# Nixie_noTube_final.net
KiCad netlist of a schematic drawn in EAGLE
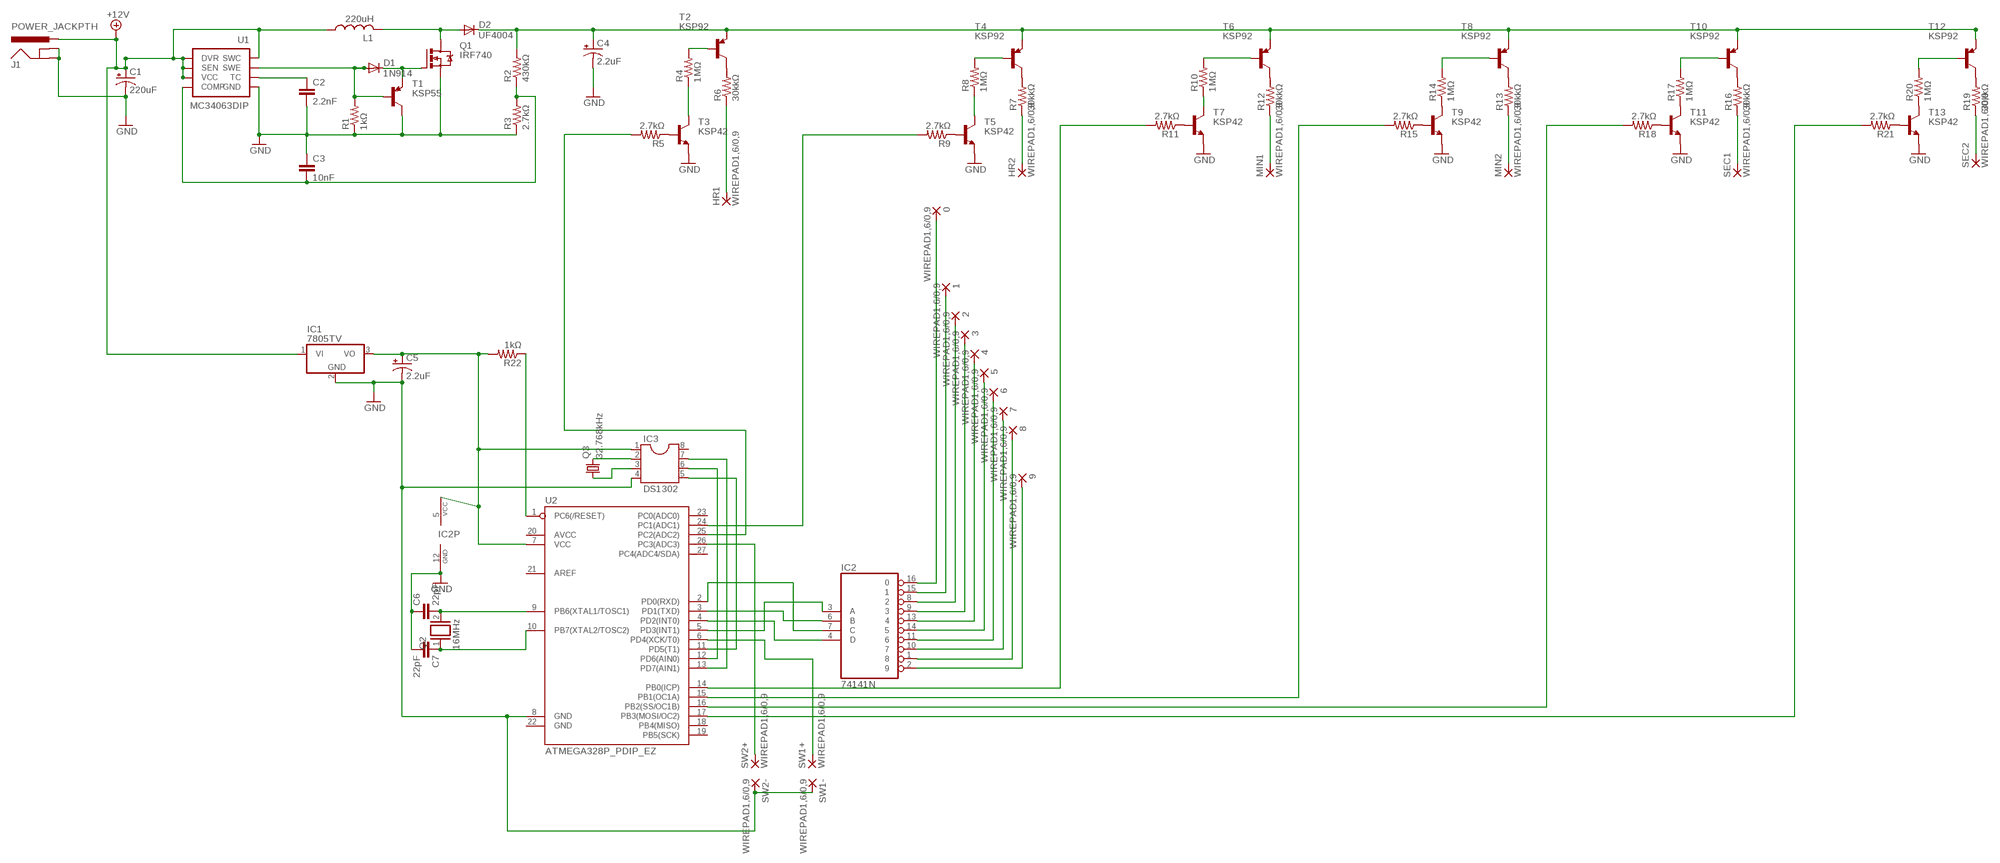
[diagram p0: schematic, sheet 1]

(export (version "E")
  (design (tool "Eeschema 10.0.6"))
  (components
    (comp (ref "0")
      (value "WIREPAD1,6/0,9")
      (footprint "eagle-import:1,6_0,9")
      (libsource (lib "eagle-import") (part "WIREPAD1,6/0,9"))
    )
    (comp (ref "1")
      (value "WIREPAD1,6/0,9")
      (footprint "eagle-import:1,6_0,9")
      (libsource (lib "eagle-import") (part "WIREPAD1,6/0,9"))
    )
    (comp (ref "2")
      (value "WIREPAD1,6/0,9")
      (footprint "eagle-import:1,6_0,9")
      (libsource (lib "eagle-import") (part "WIREPAD1,6/0,9"))
    )
    (comp (ref "3")
      (value "WIREPAD1,6/0,9")
      (footprint "eagle-import:1,6_0,9")
      (libsource (lib "eagle-import") (part "WIREPAD1,6/0,9"))
    )
    (comp (ref "4")
      (value "WIREPAD1,6/0,9")
      (footprint "eagle-import:1,6_0,9")
      (libsource (lib "eagle-import") (part "WIREPAD1,6/0,9"))
    )
    (comp (ref "5")
      (value "WIREPAD1,6/0,9")
      (footprint "eagle-import:1,6_0,9")
      (libsource (lib "eagle-import") (part "WIREPAD1,6/0,9"))
    )
    (comp (ref "6")
      (value "WIREPAD1,6/0,9")
      (footprint "eagle-import:1,6_0,9")
      (libsource (lib "eagle-import") (part "WIREPAD1,6/0,9"))
    )
    (comp (ref "7")
      (value "WIREPAD1,6/0,9")
      (footprint "eagle-import:1,6_0,9")
      (libsource (lib "eagle-import") (part "WIREPAD1,6/0,9"))
    )
    (comp (ref "8")
      (value "WIREPAD1,6/0,9")
      (footprint "eagle-import:1,6_0,9")
      (libsource (lib "eagle-import") (part "WIREPAD1,6/0,9"))
    )
    (comp (ref "9")
      (value "WIREPAD1,6/0,9")
      (footprint "eagle-import:1,6_0,9")
      (libsource (lib "eagle-import") (part "WIREPAD1,6/0,9"))
    )
    (comp (ref "C1")
      (value "220uF")
      (footprint "eagle-import:CPOL-RADIAL-100UF-25V")
      (libsource (lib "eagle-import") (part "CAP_POLPTH1"))
    )
    (comp (ref "C2")
      (value "2.2nF")
      (footprint "eagle-import:CAP-PTH-SMALLEZ")
      (libsource (lib "eagle-import") (part "CAPEZ"))
    )
    (comp (ref "C3")
      (value "10nF")
      (footprint "eagle-import:CAP-PTH-SMALLEZ")
      (libsource (lib "eagle-import") (part "CAPEZ"))
    )
    (comp (ref "C4")
      (value "2.2uF")
      (footprint "eagle-import:CPOL-RADIAL-100UF-25V")
      (libsource (lib "eagle-import") (part "CAP_POLPTH1"))
    )
    (comp (ref "C5")
      (value "2.2uF")
      (footprint "eagle-import:CPOL-RADIAL-100UF-25V")
      (libsource (lib "eagle-import") (part "CAP_POLPTH1"))
    )
    (comp (ref "C6")
      (value "22pF")
      (footprint "eagle-import:C2.5-3")
      (libsource (lib "eagle-import") (part "C2,5-3"))
    )
    (comp (ref "C7")
      (value "22pF")
      (footprint "eagle-import:C2.5-3")
      (libsource (lib "eagle-import") (part "C2,5-3"))
    )
    (comp (ref "D1")
      (value "1N914")
      (footprint "eagle-import:DO41-10")
      (libsource (lib "eagle-import") (part "1N4004"))
    )
    (comp (ref "D2")
      (value "UF4004")
      (footprint "eagle-import:DO41-10")
      (libsource (lib "eagle-import") (part "1N4004"))
    )
    (comp (ref "HR1")
      (value "WIREPAD1,6/0,9")
      (footprint "eagle-import:1,6_0,9")
      (libsource (lib "eagle-import") (part "WIREPAD1,6/0,9"))
    )
    (comp (ref "HR2")
      (value "WIREPAD1,6/0,9")
      (footprint "eagle-import:1,6_0,9")
      (libsource (lib "eagle-import") (part "WIREPAD1,6/0,9"))
    )
    (comp (ref "IC1")
      (value "7805TV")
      (footprint "eagle-import:TO220V")
      (libsource (lib "eagle-import") (part "78TV05"))
    )
    (comp (ref "IC2")
      (value "74141N")
      (footprint "eagle-import:DIL16")
      (libsource (lib "eagle-import") (part "74141N"))
    )
    (comp (ref "IC3")
      (value "DS1302")
      (footprint "eagle-import:DIL08")
      (libsource (lib "eagle-import") (part "DIL8"))
    )
    (comp (ref "J1")
      (value "POWER_JACKPTH")
      (footprint "eagle-import:POWER_JACK_PTH")
      (libsource (lib "eagle-import") (part "POWER_JACKPTH"))
    )
    (comp (ref "L1")
      (value "220uH")
      (footprint "eagle-import:6000-XXXX-RC")
      (libsource (lib "eagle-import") (part "L-US6000-XXX-RC"))
    )
    (comp (ref "MIN1")
      (value "WIREPAD1,6/0,9")
      (footprint "eagle-import:1,6_0,9")
      (libsource (lib "eagle-import") (part "WIREPAD1,6/0,9"))
    )
    (comp (ref "MIN2")
      (value "WIREPAD1,6/0,9")
      (footprint "eagle-import:1,6_0,9")
      (libsource (lib "eagle-import") (part "WIREPAD1,6/0,9"))
    )
    (comp (ref "Q1")
      (value "IRF740")
      (footprint "eagle-import:TO220BV")
      (libsource (lib "eagle-import") (part "IRF740"))
    )
    (comp (ref "Q2")
      (value "16MHz")
      (footprint "eagle-import:QS")
      (libsource (lib "eagle-import") (part "XTAL/S"))
    )
    (comp (ref "Q3")
      (value "32.768kHz")
      (footprint "eagle-import:TC26H")
      (libsource (lib "eagle-import") (part "CRYSTALTC26H"))
    )
    (comp (ref "R1")
      (value "1kΩ")
      (footprint "eagle-import:0204_7")
      (libsource (lib "eagle-import") (part "R-US_0204/7"))
    )
    (comp (ref "R2")
      (value "430kΩ")
      (footprint "eagle-import:0204_7")
      (libsource (lib "eagle-import") (part "R-US_0204/7"))
    )
    (comp (ref "R3")
      (value "2.7kΩ")
      (footprint "eagle-import:0204_7")
      (libsource (lib "eagle-import") (part "R-US_0204/7"))
    )
    (comp (ref "R4")
      (value "1MΩ")
      (footprint "eagle-import:0204_7")
      (libsource (lib "eagle-import") (part "R-US_0204/7"))
    )
    (comp (ref "R5")
      (value "2.7kΩ")
      (footprint "eagle-import:0204_7")
      (libsource (lib "eagle-import") (part "R-US_0204/7"))
    )
    (comp (ref "R6")
      (value "30kkΩ")
      (footprint "eagle-import:0204_7")
      (libsource (lib "eagle-import") (part "R-US_0204/7"))
    )
    (comp (ref "R7")
      (value "30kkΩ")
      (footprint "eagle-import:0204_7")
      (libsource (lib "eagle-import") (part "R-US_0204/7"))
    )
    (comp (ref "R8")
      (value "1MΩ")
      (footprint "eagle-import:0204_7")
      (libsource (lib "eagle-import") (part "R-US_0204/7"))
    )
    (comp (ref "R9")
      (value "2.7kΩ")
      (footprint "eagle-import:0204_7")
      (libsource (lib "eagle-import") (part "R-US_0204/7"))
    )
    (comp (ref "R10")
      (value "1MΩ")
      (footprint "eagle-import:0204_7")
      (libsource (lib "eagle-import") (part "R-US_0204/7"))
    )
    (comp (ref "R11")
      (value "2.7kΩ")
      (footprint "eagle-import:0204_7")
      (libsource (lib "eagle-import") (part "R-US_0204/7"))
    )
    (comp (ref "R12")
      (value "30kkΩ")
      (footprint "eagle-import:0204_7")
      (libsource (lib "eagle-import") (part "R-US_0204/7"))
    )
    (comp (ref "R13")
      (value "30kkΩ")
      (footprint "eagle-import:0204_7")
      (libsource (lib "eagle-import") (part "R-US_0204/7"))
    )
    (comp (ref "R14")
      (value "1MΩ")
      (footprint "eagle-import:0204_7")
      (libsource (lib "eagle-import") (part "R-US_0204/7"))
    )
    (comp (ref "R15")
      (value "2.7kΩ")
      (footprint "eagle-import:0204_7")
      (libsource (lib "eagle-import") (part "R-US_0204/7"))
    )
    (comp (ref "R16")
      (value "30kkΩ")
      (footprint "eagle-import:0204_7")
      (libsource (lib "eagle-import") (part "R-US_0204/7"))
    )
    (comp (ref "R17")
      (value "1MΩ")
      (footprint "eagle-import:0204_7")
      (libsource (lib "eagle-import") (part "R-US_0204/7"))
    )
    (comp (ref "R18")
      (value "2.7kΩ")
      (footprint "eagle-import:0204_7")
      (libsource (lib "eagle-import") (part "R-US_0204/7"))
    )
    (comp (ref "R19")
      (value "30kkΩ")
      (footprint "eagle-import:0204_7")
      (libsource (lib "eagle-import") (part "R-US_0204/7"))
    )
    (comp (ref "R20")
      (value "1MΩ")
      (footprint "eagle-import:0204_7")
      (libsource (lib "eagle-import") (part "R-US_0204/7"))
    )
    (comp (ref "R21")
      (value "2.7kΩ")
      (footprint "eagle-import:0204_7")
      (libsource (lib "eagle-import") (part "R-US_0204/7"))
    )
    (comp (ref "R22")
      (value "1kΩ")
      (footprint "eagle-import:0204_7")
      (libsource (lib "eagle-import") (part "R-US_0204/7"))
    )
    (comp (ref "SEC1")
      (value "WIREPAD1,6/0,9")
      (footprint "eagle-import:1,6_0,9")
      (libsource (lib "eagle-import") (part "WIREPAD1,6/0,9"))
    )
    (comp (ref "SEC2")
      (value "WIREPAD1,6/0,9")
      (footprint "eagle-import:1,6_0,9")
      (libsource (lib "eagle-import") (part "WIREPAD1,6/0,9"))
    )
    (comp (ref "SW1+")
      (value "WIREPAD1,6/0,9")
      (footprint "eagle-import:1,6_0,9")
      (libsource (lib "eagle-import") (part "WIREPAD1,6/0,9"))
    )
    (comp (ref "SW1-")
      (value "WIREPAD1,6/0,9")
      (footprint "eagle-import:1,6_0,9")
      (libsource (lib "eagle-import") (part "WIREPAD1,6/0,9"))
    )
    (comp (ref "SW2+")
      (value "WIREPAD1,6/0,9")
      (footprint "eagle-import:1,6_0,9")
      (libsource (lib "eagle-import") (part "WIREPAD1,6/0,9"))
    )
    (comp (ref "SW2-")
      (value "WIREPAD1,6/0,9")
      (footprint "eagle-import:1,6_0,9")
      (libsource (lib "eagle-import") (part "WIREPAD1,6/0,9"))
    )
    (comp (ref "T1")
      (value "KSP55")
      (footprint "eagle-import:TO92-EBC")
      (libsource (lib "eagle-import") (part "transistor-neu-to92_-PNP-TO92-EBC"))
    )
    (comp (ref "T2")
      (value "KSP92")
      (footprint "eagle-import:TO92")
      (libsource (lib "eagle-import") (part "-PNP-TO92"))
    )
    (comp (ref "T3")
      (value "KSP42")
      (footprint "eagle-import:TO92")
      (libsource (lib "eagle-import") (part "-NPN-TO92"))
    )
    (comp (ref "T4")
      (value "KSP92")
      (footprint "eagle-import:TO92")
      (libsource (lib "eagle-import") (part "-PNP-TO92"))
    )
    (comp (ref "T5")
      (value "KSP42")
      (footprint "eagle-import:TO92")
      (libsource (lib "eagle-import") (part "-NPN-TO92"))
    )
    (comp (ref "T6")
      (value "KSP92")
      (footprint "eagle-import:TO92")
      (libsource (lib "eagle-import") (part "-PNP-TO92"))
    )
    (comp (ref "T7")
      (value "KSP42")
      (footprint "eagle-import:TO92")
      (libsource (lib "eagle-import") (part "-NPN-TO92"))
    )
    (comp (ref "T8")
      (value "KSP92")
      (footprint "eagle-import:TO92")
      (libsource (lib "eagle-import") (part "-PNP-TO92"))
    )
    (comp (ref "T9")
      (value "KSP42")
      (footprint "eagle-import:TO92")
      (libsource (lib "eagle-import") (part "-NPN-TO92"))
    )
    (comp (ref "T10")
      (value "KSP92")
      (footprint "eagle-import:TO92")
      (libsource (lib "eagle-import") (part "-PNP-TO92"))
    )
    (comp (ref "T11")
      (value "KSP42")
      (footprint "eagle-import:TO92")
      (libsource (lib "eagle-import") (part "-NPN-TO92"))
    )
    (comp (ref "T12")
      (value "KSP92")
      (footprint "eagle-import:TO92")
      (libsource (lib "eagle-import") (part "-PNP-TO92"))
    )
    (comp (ref "T13")
      (value "KSP42")
      (footprint "eagle-import:TO92")
      (libsource (lib "eagle-import") (part "-NPN-TO92"))
    )
    (comp (ref "U1")
      (value "MC34063DIP")
      (footprint "eagle-import:DIP-08")
      (libsource (lib "eagle-import") (part "MC34063DIP"))
    )
    (comp (ref "U2")
      (value "ATMEGA328P_PDIP_EZ")
      (footprint "eagle-import:DIL28-EZ")
      (libsource (lib "eagle-import") (part "ATMEGA328P_PDIP_EZ"))
    )
  )
  (nets
    (net (code "1") (name "+12V") (class "Default")
      (node (ref "C1") (pin "1") (pinfunction "+_1") (pintype "passive"))
      (node (ref "IC1") (pin "1") (pinfunction "VI_1") (pintype "input"))
      (node (ref "J1") (pin "PWR") (pinfunction "PWR_PWR") (pintype "bidirectional"))
      (node (ref "L1") (pin "1") (pinfunction "1_1") (pintype "passive"))
      (node (ref "U1") (pin "1") (pinfunction "SWC_1") (pintype "bidirectional"))
      (node (ref "U1") (pin "6") (pinfunction "VCC_6") (pintype "bidirectional"))
      (node (ref "U1") (pin "7") (pinfunction "SEN_7") (pintype "bidirectional"))
      (node (ref "U1") (pin "8") (pinfunction "DVR_8") (pintype "bidirectional"))
    )
    (net (code "2") (name "GND") (class "Default")
      (node (ref "C1") (pin "2") (pinfunction "-_2") (pintype "passive"))
      (node (ref "C2") (pin "2") (pinfunction "2_2") (pintype "passive"))
      (node (ref "C3") (pin "1") (pinfunction "1_1") (pintype "passive"))
      (node (ref "C4") (pin "2") (pinfunction "-_2") (pintype "passive"))
      (node (ref "C5") (pin "2") (pinfunction "-_2") (pintype "passive"))
      (node (ref "C6") (pin "1") (pinfunction "1_1") (pintype "passive"))
      (node (ref "C7") (pin "2") (pinfunction "2_2") (pintype "passive"))
      (node (ref "IC1") (pin "2") (pinfunction "GND_2") (pintype "passive"))
      (node (ref "IC2") (pin "12") (pinfunction "GND_12") (pintype "power_in"))
      (node (ref "IC3") (pin "4") (pinfunction "4_4") (pintype "passive"))
      (node (ref "J1") (pin "GND") (pinfunction "GND_GND") (pintype "bidirectional"))
      (node (ref "J1") (pin "GNDBREAK") (pinfunction "GNDBREAK_GNDBREAK") (pintype "bidirectional"))
      (node (ref "Q1") (pin "S") (pinfunction "S_S") (pintype "passive"))
      (node (ref "R1") (pin "1") (pinfunction "1_1") (pintype "passive"))
      (node (ref "R3") (pin "1") (pinfunction "1_1") (pintype "passive"))
      (node (ref "SW1-") (pin "1") (pinfunction "P_1") (pintype "passive"))
      (node (ref "SW2-") (pin "1") (pinfunction "P_1") (pintype "passive"))
      (node (ref "T1") (pin "C") (pinfunction "C_C") (pintype "passive"))
      (node (ref "T11") (pin "1") (pinfunction "E_1") (pintype "passive"))
      (node (ref "T13") (pin "1") (pinfunction "E_1") (pintype "passive"))
      (node (ref "T3") (pin "1") (pinfunction "E_1") (pintype "passive"))
      (node (ref "T5") (pin "1") (pinfunction "E_1") (pintype "passive"))
      (node (ref "T7") (pin "1") (pinfunction "E_1") (pintype "passive"))
      (node (ref "T9") (pin "1") (pinfunction "E_1") (pintype "passive"))
      (node (ref "U1") (pin "4") (pinfunction "GND_4") (pintype "bidirectional"))
      (node (ref "U2") (pin "8") (pinfunction "GND_8") (pintype "bidirectional"))
    )
    (net (code "3") (name "Net-(0-P)") (class "Default")
      (node (ref "0") (pin "1") (pinfunction "P_1") (pintype "passive"))
      (node (ref "IC2") (pin "16") (pinfunction "0_16") (pintype "open_collector"))
    )
    (net (code "4") (name "Net-(1-P)") (class "Default")
      (node (ref "1") (pin "1") (pinfunction "P_1") (pintype "passive"))
      (node (ref "IC2") (pin "15") (pinfunction "1_15") (pintype "open_collector"))
    )
    (net (code "5") (name "Net-(2-P)") (class "Default")
      (node (ref "2") (pin "1") (pinfunction "P_1") (pintype "passive"))
      (node (ref "IC2") (pin "8") (pinfunction "2_8") (pintype "open_collector"))
    )
    (net (code "6") (name "Net-(3-P)") (class "Default")
      (node (ref "3") (pin "1") (pinfunction "P_1") (pintype "passive"))
      (node (ref "IC2") (pin "9") (pinfunction "3_9") (pintype "open_collector"))
    )
    (net (code "7") (name "Net-(4-P)") (class "Default")
      (node (ref "4") (pin "1") (pinfunction "P_1") (pintype "passive"))
      (node (ref "IC2") (pin "13") (pinfunction "4_13") (pintype "open_collector"))
    )
    (net (code "8") (name "Net-(5-P)") (class "Default")
      (node (ref "5") (pin "1") (pinfunction "P_1") (pintype "passive"))
      (node (ref "IC2") (pin "14") (pinfunction "5_14") (pintype "open_collector"))
    )
    (net (code "9") (name "Net-(6-P)") (class "Default")
      (node (ref "6") (pin "1") (pinfunction "P_1") (pintype "passive"))
      (node (ref "IC2") (pin "11") (pinfunction "6_11") (pintype "open_collector"))
    )
    (net (code "10") (name "Net-(7-P)") (class "Default")
      (node (ref "7") (pin "1") (pinfunction "P_1") (pintype "passive"))
      (node (ref "IC2") (pin "10") (pinfunction "7_10") (pintype "open_collector"))
    )
    (net (code "11") (name "Net-(8-P)") (class "Default")
      (node (ref "8") (pin "1") (pinfunction "P_1") (pintype "passive"))
      (node (ref "IC2") (pin "1") (pinfunction "8_1") (pintype "open_collector"))
    )
    (net (code "12") (name "Net-(9-P)") (class "Default")
      (node (ref "9") (pin "1") (pinfunction "P_1") (pintype "passive"))
      (node (ref "IC2") (pin "2") (pinfunction "9_2") (pintype "open_collector"))
    )
    (net (code "13") (name "Net-(C4-+)") (class "Default")
      (node (ref "C4") (pin "1") (pinfunction "+_1") (pintype "passive"))
      (node (ref "D2") (pin "C") (pinfunction "C_C") (pintype "passive"))
      (node (ref "R2") (pin "2") (pinfunction "2_2") (pintype "passive"))
      (node (ref "T10") (pin "1") (pinfunction "E_1") (pintype "passive"))
      (node (ref "T12") (pin "1") (pinfunction "E_1") (pintype "passive"))
      (node (ref "T2") (pin "1") (pinfunction "E_1") (pintype "passive"))
      (node (ref "T4") (pin "1") (pinfunction "E_1") (pintype "passive"))
      (node (ref "T6") (pin "1") (pinfunction "E_1") (pintype "passive"))
      (node (ref "T8") (pin "1") (pinfunction "E_1") (pintype "passive"))
    )
    (net (code "14") (name "Net-(C5-+)") (class "Default")
      (node (ref "C5") (pin "1") (pinfunction "+_1") (pintype "passive"))
      (node (ref "IC1") (pin "3") (pinfunction "VO_3") (pintype "passive"))
      (node (ref "IC2") (pin "5") (pinfunction "VCC_5") (pintype "power_in"))
      (node (ref "IC3") (pin "1") (pinfunction "1_1") (pintype "passive"))
      (node (ref "R22") (pin "2") (pinfunction "2_2") (pintype "passive"))
      (node (ref "U2") (pin "7") (pinfunction "VCC_7") (pintype "bidirectional"))
    )
    (net (code "15") (name "Net-(D1-PadC)") (class "Default")
      (node (ref "D1") (pin "C") (pinfunction "C_C") (pintype "passive"))
      (node (ref "Q1") (pin "G") (pinfunction "G_G") (pintype "passive"))
      (node (ref "T1") (pin "E") (pinfunction "E_E") (pintype "passive"))
    )
    (net (code "16") (name "Net-(D2-PadA)") (class "Default")
      (node (ref "D2") (pin "A") (pinfunction "A_A") (pintype "passive"))
      (node (ref "L1") (pin "2") (pinfunction "2_2") (pintype "passive"))
      (node (ref "Q1") (pin "D") (pinfunction "D_D") (pintype "passive"))
    )
    (net (code "17") (name "Net-(HR1-P)") (class "Default")
      (node (ref "HR1") (pin "1") (pinfunction "P_1") (pintype "passive"))
      (node (ref "R6") (pin "1") (pinfunction "1_1") (pintype "passive"))
    )
    (net (code "18") (name "Net-(HR2-P)") (class "Default")
      (node (ref "HR2") (pin "1") (pinfunction "P_1") (pintype "passive"))
      (node (ref "R7") (pin "1") (pinfunction "1_1") (pintype "passive"))
    )
    (net (code "19") (name "Net-(IC2A-A)") (class "Default")
      (node (ref "IC2") (pin "3") (pinfunction "A_3") (pintype "input"))
      (node (ref "U2") (pin "5") (pinfunction "PD3(INT1)_5") (pintype "bidirectional"))
    )
    (net (code "20") (name "Net-(IC2A-B)") (class "Default")
      (node (ref "IC2") (pin "6") (pinfunction "B_6") (pintype "input"))
      (node (ref "U2") (pin "3") (pinfunction "PD1(TXD)_3") (pintype "bidirectional"))
    )
    (net (code "21") (name "Net-(IC2A-C)") (class "Default")
      (node (ref "IC2") (pin "7") (pinfunction "C_7") (pintype "input"))
      (node (ref "U2") (pin "2") (pinfunction "PD0(RXD)_2") (pintype "bidirectional"))
    )
    (net (code "22") (name "Net-(IC2A-D)") (class "Default")
      (node (ref "IC2") (pin "4") (pinfunction "D_4") (pintype "input"))
      (node (ref "U2") (pin "4") (pinfunction "PD2(INT0)_4") (pintype "bidirectional"))
    )
    (net (code "23") (name "Net-(IC3-Pad2)") (class "Default")
      (node (ref "IC3") (pin "2") (pinfunction "2_2") (pintype "passive"))
      (node (ref "Q3") (pin "2") (pinfunction "2_2") (pintype "passive"))
    )
    (net (code "24") (name "Net-(IC3-Pad3)") (class "Default")
      (node (ref "IC3") (pin "3") (pinfunction "3_3") (pintype "passive"))
      (node (ref "Q3") (pin "1") (pinfunction "1_1") (pintype "passive"))
    )
    (net (code "25") (name "Net-(MIN1-P)") (class "Default")
      (node (ref "MIN1") (pin "1") (pinfunction "P_1") (pintype "passive"))
      (node (ref "R12") (pin "1") (pinfunction "1_1") (pintype "passive"))
    )
    (net (code "26") (name "Net-(MIN2-P)") (class "Default")
      (node (ref "MIN2") (pin "1") (pinfunction "P_1") (pintype "passive"))
      (node (ref "R13") (pin "1") (pinfunction "1_1") (pintype "passive"))
    )
    (net (code "27") (name "Net-(SEC1-P)") (class "Default")
      (node (ref "R16") (pin "1") (pinfunction "1_1") (pintype "passive"))
      (node (ref "SEC1") (pin "1") (pinfunction "P_1") (pintype "passive"))
    )
    (net (code "28") (name "Net-(SEC2-P)") (class "Default")
      (node (ref "R19") (pin "1") (pinfunction "1_1") (pintype "passive"))
      (node (ref "SEC2") (pin "1") (pinfunction "P_1") (pintype "passive"))
    )
    (net (code "29") (name "Net-(SW1+-P)") (class "Default")
      (node (ref "SW1+") (pin "1") (pinfunction "P_1") (pintype "passive"))
      (node (ref "U2") (pin "6") (pinfunction "PD4(XCK/T0)_6") (pintype "bidirectional"))
    )
    (net (code "30") (name "Net-(SW2+-P)") (class "Default")
      (node (ref "SW2+") (pin "1") (pinfunction "P_1") (pintype "passive"))
      (node (ref "U2") (pin "26") (pinfunction "PC3(ADC3)_26") (pintype "bidirectional"))
    )
    (net (code "31") (name "Net-(T2-B)") (class "Default")
      (node (ref "R4") (pin "2") (pinfunction "2_2") (pintype "passive"))
      (node (ref "T2") (pin "2") (pinfunction "B_2") (pintype "passive"))
    )
    (net (code "32") (name "Net-(T2-C)") (class "Default")
      (node (ref "R6") (pin "2") (pinfunction "2_2") (pintype "passive"))
      (node (ref "T2") (pin "3") (pinfunction "C_3") (pintype "passive"))
    )
    (net (code "33") (name "Net-(T3-B)") (class "Default")
      (node (ref "R5") (pin "1") (pinfunction "1_1") (pintype "passive"))
      (node (ref "T3") (pin "2") (pinfunction "B_2") (pintype "passive"))
    )
    (net (code "34") (name "Net-(T3-C)") (class "Default")
      (node (ref "R4") (pin "1") (pinfunction "1_1") (pintype "passive"))
      (node (ref "T3") (pin "3") (pinfunction "C_3") (pintype "passive"))
    )
    (net (code "35") (name "Net-(T4-B)") (class "Default")
      (node (ref "R8") (pin "2") (pinfunction "2_2") (pintype "passive"))
      (node (ref "T4") (pin "2") (pinfunction "B_2") (pintype "passive"))
    )
    (net (code "36") (name "Net-(T4-C)") (class "Default")
      (node (ref "R7") (pin "2") (pinfunction "2_2") (pintype "passive"))
      (node (ref "T4") (pin "3") (pinfunction "C_3") (pintype "passive"))
    )
    (net (code "37") (name "Net-(T5-B)") (class "Default")
      (node (ref "R9") (pin "1") (pinfunction "1_1") (pintype "passive"))
      (node (ref "T5") (pin "2") (pinfunction "B_2") (pintype "passive"))
    )
    (net (code "38") (name "Net-(T5-C)") (class "Default")
      (node (ref "R8") (pin "1") (pinfunction "1_1") (pintype "passive"))
      (node (ref "T5") (pin "3") (pinfunction "C_3") (pintype "passive"))
    )
    (net (code "39") (name "Net-(T6-B)") (class "Default")
      (node (ref "R10") (pin "2") (pinfunction "2_2") (pintype "passive"))
      (node (ref "T6") (pin "2") (pinfunction "B_2") (pintype "passive"))
    )
    (net (code "40") (name "Net-(T6-C)") (class "Default")
      (node (ref "R12") (pin "2") (pinfunction "2_2") (pintype "passive"))
      (node (ref "T6") (pin "3") (pinfunction "C_3") (pintype "passive"))
    )
    (net (code "41") (name "Net-(T7-B)") (class "Default")
      (node (ref "R11") (pin "1") (pinfunction "1_1") (pintype "passive"))
      (node (ref "T7") (pin "2") (pinfunction "B_2") (pintype "passive"))
    )
    (net (code "42") (name "Net-(T7-C)") (class "Default")
      (node (ref "R10") (pin "1") (pinfunction "1_1") (pintype "passive"))
      (node (ref "T7") (pin "3") (pinfunction "C_3") (pintype "passive"))
    )
    (net (code "43") (name "Net-(T8-B)") (class "Default")
      (node (ref "R14") (pin "2") (pinfunction "2_2") (pintype "passive"))
      (node (ref "T8") (pin "2") (pinfunction "B_2") (pintype "passive"))
    )
    (net (code "44") (name "Net-(T8-C)") (class "Default")
      (node (ref "R13") (pin "2") (pinfunction "2_2") (pintype "passive"))
      (node (ref "T8") (pin "3") (pinfunction "C_3") (pintype "passive"))
    )
    (net (code "45") (name "Net-(T9-B)") (class "Default")
      (node (ref "R15") (pin "1") (pinfunction "1_1") (pintype "passive"))
      (node (ref "T9") (pin "2") (pinfunction "B_2") (pintype "passive"))
    )
    (net (code "46") (name "Net-(T9-C)") (class "Default")
      (node (ref "R14") (pin "1") (pinfunction "1_1") (pintype "passive"))
      (node (ref "T9") (pin "3") (pinfunction "C_3") (pintype "passive"))
    )
    (net (code "47") (name "Net-(T10-B)") (class "Default")
      (node (ref "R17") (pin "2") (pinfunction "2_2") (pintype "passive"))
      (node (ref "T10") (pin "2") (pinfunction "B_2") (pintype "passive"))
    )
    (net (code "48") (name "Net-(T10-C)") (class "Default")
      (node (ref "R16") (pin "2") (pinfunction "2_2") (pintype "passive"))
      (node (ref "T10") (pin "3") (pinfunction "C_3") (pintype "passive"))
    )
    (net (code "49") (name "Net-(T11-B)") (class "Default")
      (node (ref "R18") (pin "1") (pinfunction "1_1") (pintype "passive"))
      (node (ref "T11") (pin "2") (pinfunction "B_2") (pintype "passive"))
    )
    (net (code "50") (name "Net-(T11-C)") (class "Default")
      (node (ref "R17") (pin "1") (pinfunction "1_1") (pintype "passive"))
      (node (ref "T11") (pin "3") (pinfunction "C_3") (pintype "passive"))
    )
    (net (code "51") (name "Net-(T12-B)") (class "Default")
      (node (ref "R20") (pin "2") (pinfunction "2_2") (pintype "passive"))
      (node (ref "T12") (pin "2") (pinfunction "B_2") (pintype "passive"))
    )
    (net (code "52") (name "Net-(T12-C)") (class "Default")
      (node (ref "R19") (pin "2") (pinfunction "2_2") (pintype "passive"))
      (node (ref "T12") (pin "3") (pinfunction "C_3") (pintype "passive"))
    )
    (net (code "53") (name "Net-(T13-B)") (class "Default")
      (node (ref "R21") (pin "1") (pinfunction "1_1") (pintype "passive"))
      (node (ref "T13") (pin "2") (pinfunction "B_2") (pintype "passive"))
    )
    (net (code "54") (name "Net-(T13-C)") (class "Default")
      (node (ref "R20") (pin "1") (pinfunction "1_1") (pintype "passive"))
      (node (ref "T13") (pin "3") (pinfunction "C_3") (pintype "passive"))
    )
    (net (code "55") (name "Net-(U1-COMP)") (class "Default")
      (node (ref "C3") (pin "2") (pinfunction "2_2") (pintype "passive"))
      (node (ref "R2") (pin "1") (pinfunction "1_1") (pintype "passive"))
      (node (ref "R3") (pin "2") (pinfunction "2_2") (pintype "passive"))
      (node (ref "U1") (pin "5") (pinfunction "COMP_5") (pintype "bidirectional"))
    )
    (net (code "56") (name "Net-(U1-SWE)") (class "Default")
      (node (ref "D1") (pin "A") (pinfunction "A_A") (pintype "passive"))
      (node (ref "R1") (pin "2") (pinfunction "2_2") (pintype "passive"))
      (node (ref "T1") (pin "B") (pinfunction "B_B") (pintype "passive"))
      (node (ref "U1") (pin "2") (pinfunction "SWE_2") (pintype "bidirectional"))
    )
    (net (code "57") (name "Net-(U1-TC)") (class "Default")
      (node (ref "C2") (pin "1") (pinfunction "1_1") (pintype "passive"))
      (node (ref "U1") (pin "3") (pinfunction "TC_3") (pintype "bidirectional"))
    )
    (net (code "58") (name "Net-(U2-PB0(ICP))") (class "Default")
      (node (ref "R11") (pin "2") (pinfunction "2_2") (pintype "passive"))
      (node (ref "U2") (pin "14") (pinfunction "PB0(ICP)_14") (pintype "bidirectional"))
    )
    (net (code "59") (name "Net-(U2-PB1(OC1A))") (class "Default")
      (node (ref "R15") (pin "2") (pinfunction "2_2") (pintype "passive"))
      (node (ref "U2") (pin "15") (pinfunction "PB1(OC1A)_15") (pintype "bidirectional"))
    )
    (net (code "60") (name "Net-(U2-PB2(SS{slash}OC1B))") (class "Default")
      (node (ref "R18") (pin "2") (pinfunction "2_2") (pintype "passive"))
      (node (ref "U2") (pin "16") (pinfunction "PB2(SS/OC1B)_16") (pintype "bidirectional"))
    )
    (net (code "61") (name "Net-(U2-PB3(MOSI{slash}OC2))") (class "Default")
      (node (ref "R21") (pin "2") (pinfunction "2_2") (pintype "passive"))
      (node (ref "U2") (pin "17") (pinfunction "PB3(MOSI/OC2)_17") (pintype "bidirectional"))
    )
    (net (code "62") (name "Net-(U2-PB6(XTAL1{slash}TOSC1))") (class "Default")
      (node (ref "C6") (pin "2") (pinfunction "2_2") (pintype "passive"))
      (node (ref "Q2") (pin "2") (pinfunction "2_2") (pintype "passive"))
      (node (ref "U2") (pin "9") (pinfunction "PB6(XTAL1/TOSC1)_9") (pintype "bidirectional"))
    )
    (net (code "63") (name "Net-(U2-PB7(XTAL2{slash}TOSC2))") (class "Default")
      (node (ref "C7") (pin "1") (pinfunction "1_1") (pintype "passive"))
      (node (ref "Q2") (pin "1") (pinfunction "1_1") (pintype "passive"))
      (node (ref "U2") (pin "10") (pinfunction "PB7(XTAL2/TOSC2)_10") (pintype "bidirectional"))
    )
    (net (code "64") (name "Net-(U2-PC1(ADC1))") (class "Default")
      (node (ref "R9") (pin "2") (pinfunction "2_2") (pintype "passive"))
      (node (ref "U2") (pin "24") (pinfunction "PC1(ADC1)_24") (pintype "bidirectional"))
    )
    (net (code "65") (name "Net-(U2-PC2(ADC2))") (class "Default")
      (node (ref "R5") (pin "2") (pinfunction "2_2") (pintype "passive"))
      (node (ref "U2") (pin "25") (pinfunction "PC2(ADC2)_25") (pintype "bidirectional"))
    )
    (net (code "66") (name "Net-(U2-PC6({slash}RESET))") (class "Default")
      (node (ref "R22") (pin "1") (pinfunction "1_1") (pintype "passive"))
      (node (ref "U2") (pin "1") (pinfunction "PC6(/RESET)_1") (pintype "bidirectional"))
    )
    (net (code "67") (name "Net-(U2-PD5(T1))") (class "Default")
      (node (ref "IC3") (pin "5") (pinfunction "5_5") (pintype "passive"))
      (node (ref "U2") (pin "11") (pinfunction "PD5(T1)_11") (pintype "bidirectional"))
    )
    (net (code "68") (name "Net-(U2-PD6(AIN0))") (class "Default")
      (node (ref "IC3") (pin "6") (pinfunction "6_6") (pintype "passive"))
      (node (ref "U2") (pin "12") (pinfunction "PD6(AIN0)_12") (pintype "bidirectional"))
    )
    (net (code "69") (name "Net-(U2-PD7(AIN1))") (class "Default")
      (node (ref "IC3") (pin "7") (pinfunction "7_7") (pintype "passive"))
      (node (ref "U2") (pin "13") (pinfunction "PD7(AIN1)_13") (pintype "bidirectional"))
    )
    (net (code "70") (name "unconnected-(IC3-Pad8)") (class "Default")
      (node (ref "IC3") (pin "8") (pinfunction "8_8") (pintype "passive"))
    )
    (net (code "71") (name "unconnected-(U2-AREF-Pad21)") (class "Default")
      (node (ref "U2") (pin "21") (pinfunction "AREF_21") (pintype "bidirectional"))
    )
    (net (code "72") (name "unconnected-(U2-AVCC-Pad20)") (class "Default")
      (node (ref "U2") (pin "20") (pinfunction "AVCC_20") (pintype "bidirectional"))
    )
    (net (code "73") (name "unconnected-(U2-GND-Pad22)") (class "Default")
      (node (ref "U2") (pin "22") (pinfunction "GND_22") (pintype "bidirectional"))
    )
    (net (code "74") (name "unconnected-(U2-PB4(MISO)-Pad18)") (class "Default")
      (node (ref "U2") (pin "18") (pinfunction "PB4(MISO)_18") (pintype "bidirectional"))
    )
    (net (code "75") (name "unconnected-(U2-PB5(SCK)-Pad19)") (class "Default")
      (node (ref "U2") (pin "19") (pinfunction "PB5(SCK)_19") (pintype "bidirectional"))
    )
    (net (code "76") (name "unconnected-(U2-PC0(ADC0)-Pad23)") (class "Default")
      (node (ref "U2") (pin "23") (pinfunction "PC0(ADC0)_23") (pintype "bidirectional"))
    )
    (net (code "77") (name "unconnected-(U2-PC4(ADC4{slash}SDA)-Pad27)") (class "Default")
      (node (ref "U2") (pin "27") (pinfunction "PC4(ADC4/SDA)_27") (pintype "bidirectional"))
    )
  )
)
